# kolorofon.net
KiCad netlist of a schematic drawn in EAGLE
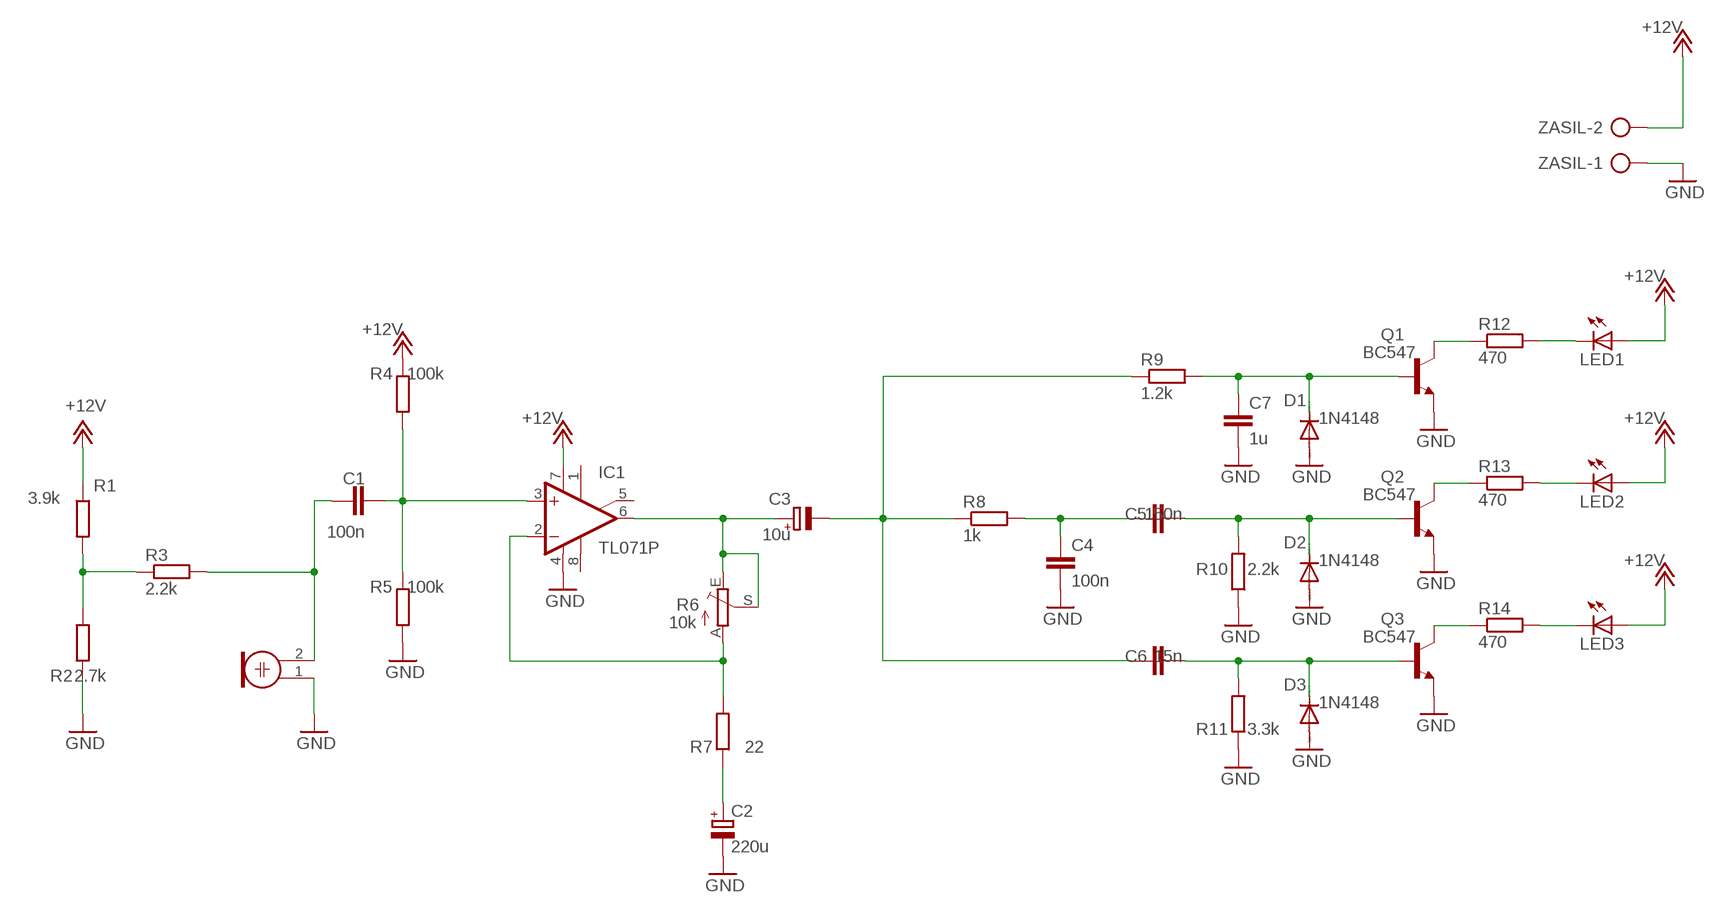
[diagram p0: schematic, sheet 1]

(export (version "E")
  (design (tool "Eeschema 10.0.6"))
  (components
    (comp (ref "C1")
      (value "100n")
      (footprint "eagle-import:C050-025X075")
      (libsource (lib "eagle-import") (part "C-EU050-025X075"))
    )
    (comp (ref "C2")
      (value "220u")
      (footprint "eagle-import:E2,5-6E")
      (libsource (lib "eagle-import") (part "resistor_CPOL-EUE2,5-6E"))
    )
    (comp (ref "C3")
      (value "10u")
      (footprint "eagle-import:E2-5")
      (libsource (lib "eagle-import") (part "CPOL-EUE2-5"))
    )
    (comp (ref "C4")
      (value "100n")
      (footprint "eagle-import:C050-025X075")
      (libsource (lib "eagle-import") (part "C-EU050-025X075"))
    )
    (comp (ref "C5")
      (value "150n")
      (footprint "eagle-import:C050-025X075")
      (libsource (lib "eagle-import") (part "C-EU050-025X075"))
    )
    (comp (ref "C6")
      (value "15n")
      (footprint "eagle-import:C050-025X075")
      (libsource (lib "eagle-import") (part "C-EU050-025X075"))
    )
    (comp (ref "C7")
      (value "1u")
      (footprint "eagle-import:C050-045X075")
      (libsource (lib "eagle-import") (part "C-EU050-045X075"))
    )
    (comp (ref "D1")
      (value "1N4148")
      (footprint "eagle-import:DO35-7")
      (libsource (lib "eagle-import") (part "1N4148DO35-7"))
    )
    (comp (ref "D2")
      (value "1N4148")
      (footprint "eagle-import:DO35-7")
      (libsource (lib "eagle-import") (part "1N4148DO35-7"))
    )
    (comp (ref "D3")
      (value "1N4148")
      (footprint "eagle-import:DO35-7")
      (libsource (lib "eagle-import") (part "1N4148DO35-7"))
    )
    (comp (ref "IC1")
      (value "TL071P")
      (footprint "eagle-import:DIL08")
      (libsource (lib "eagle-import") (part "TL071P"))
    )
    (comp (ref "LED1")
      (value "LED5MM")
      (footprint "eagle-import:LED5MM")
      (libsource (lib "eagle-import") (part "LED5MM"))
    )
    (comp (ref "LED2")
      (value "LED5MM")
      (footprint "eagle-import:LED5MM")
      (libsource (lib "eagle-import") (part "LED5MM"))
    )
    (comp (ref "LED3")
      (value "LED5MM")
      (footprint "eagle-import:LED5MM")
      (libsource (lib "eagle-import") (part "LED5MM"))
    )
    (comp (ref "M1")
      (value "WM.64PN")
      (footprint "eagle-import:WM-64PN")
      (libsource (lib "eagle-import") (part "ELECTRET_MICROPHON-WM.64PN"))
    )
    (comp (ref "Q1")
      (value "BC547")
      (footprint "eagle-import:TO92")
      (libsource (lib "eagle-import") (part "BC547"))
    )
    (comp (ref "Q2")
      (value "BC547")
      (footprint "eagle-import:TO92")
      (libsource (lib "eagle-import") (part "BC547"))
    )
    (comp (ref "Q3")
      (value "BC547")
      (footprint "eagle-import:TO92")
      (libsource (lib "eagle-import") (part "BC547"))
    )
    (comp (ref "R1")
      (value "3.9k")
      (footprint "eagle-import:0204_7")
      (libsource (lib "eagle-import") (part "R-EU_0204/7"))
    )
    (comp (ref "R2")
      (value "2.7k")
      (footprint "eagle-import:0204_7")
      (libsource (lib "eagle-import") (part "R-EU_0204/7"))
    )
    (comp (ref "R3")
      (value "2.2k")
      (footprint "eagle-import:0204_7")
      (libsource (lib "eagle-import") (part "R-EU_0204/7"))
    )
    (comp (ref "R4")
      (value "100k")
      (footprint "eagle-import:0204_7")
      (libsource (lib "eagle-import") (part "R-EU_0204/7"))
    )
    (comp (ref "R5")
      (value "100k")
      (footprint "eagle-import:0204_7")
      (libsource (lib "eagle-import") (part "R-EU_0204/7"))
    )
    (comp (ref "R6")
      (value "10k")
      (footprint "eagle-import:S64Y")
      (libsource (lib "eagle-import") (part "TRIM_EU-S64Y"))
    )
    (comp (ref "R7")
      (value "22")
      (footprint "eagle-import:0204_7")
      (libsource (lib "eagle-import") (part "R-EU_0204/7"))
    )
    (comp (ref "R8")
      (value "1k")
      (footprint "eagle-import:0204_7")
      (libsource (lib "eagle-import") (part "R-EU_0204/7"))
    )
    (comp (ref "R9")
      (value "1.2k")
      (footprint "eagle-import:0204_7")
      (libsource (lib "eagle-import") (part "R-EU_0204/7"))
    )
    (comp (ref "R10")
      (value "2.2k")
      (footprint "eagle-import:0204_7")
      (libsource (lib "eagle-import") (part "R-EU_0204/7"))
    )
    (comp (ref "R11")
      (value "3.3k")
      (footprint "eagle-import:0204_7")
      (libsource (lib "eagle-import") (part "R-EU_0204/7"))
    )
    (comp (ref "R12")
      (value "470")
      (footprint "eagle-import:0204_7")
      (libsource (lib "eagle-import") (part "R-EU_0204/7"))
    )
    (comp (ref "R13")
      (value "470")
      (footprint "eagle-import:0204_7")
      (libsource (lib "eagle-import") (part "R-EU_0204/7"))
    )
    (comp (ref "R14")
      (value "470")
      (footprint "eagle-import:0204_7")
      (libsource (lib "eagle-import") (part "R-EU_0204/7"))
    )
    (comp (ref "ZASIL")
      (value "AK300/2")
      (footprint "eagle-import:AK300_2")
      (libsource (lib "eagle-import") (part "AK300/2"))
    )
  )
  (nets
    (net (code "1") (name "+12V") (class "Default")
      (node (ref "IC1") (pin "7") (pinfunction "V+_7") (pintype "power_in"))
      (node (ref "LED1") (pin "A") (pinfunction "A_A") (pintype "passive"))
      (node (ref "LED2") (pin "A") (pinfunction "A_A") (pintype "passive"))
      (node (ref "LED3") (pin "A") (pinfunction "A_A") (pintype "passive"))
      (node (ref "R1") (pin "1") (pinfunction "1_1") (pintype "passive"))
      (node (ref "R4") (pin "2") (pinfunction "2_2") (pintype "passive"))
      (node (ref "ZASIL") (pin "2") (pinfunction "KL_2") (pintype "passive"))
    )
    (net (code "2") (name "GND") (class "Default")
      (node (ref "C2") (pin "-") (pinfunction "-_-") (pintype "passive"))
      (node (ref "C4") (pin "2") (pinfunction "2_2") (pintype "passive"))
      (node (ref "C7") (pin "2") (pinfunction "2_2") (pintype "passive"))
      (node (ref "D1") (pin "A") (pinfunction "A_A") (pintype "passive"))
      (node (ref "D2") (pin "A") (pinfunction "A_A") (pintype "passive"))
      (node (ref "D3") (pin "A") (pinfunction "A_A") (pintype "passive"))
      (node (ref "IC1") (pin "4") (pinfunction "V-_4") (pintype "power_in"))
      (node (ref "M1") (pin "1") (pinfunction "1_1") (pintype "passive"))
      (node (ref "Q1") (pin "1") (pinfunction "E_1") (pintype "passive"))
      (node (ref "Q2") (pin "1") (pinfunction "E_1") (pintype "passive"))
      (node (ref "Q3") (pin "1") (pinfunction "E_1") (pintype "passive"))
      (node (ref "R10") (pin "1") (pinfunction "1_1") (pintype "passive"))
      (node (ref "R11") (pin "1") (pinfunction "1_1") (pintype "passive"))
      (node (ref "R2") (pin "1") (pinfunction "1_1") (pintype "passive"))
      (node (ref "R5") (pin "1") (pinfunction "1_1") (pintype "passive"))
      (node (ref "ZASIL") (pin "1") (pinfunction "KL_1") (pintype "passive"))
    )
    (net (code "3") (name "Net-(C1-Pad1)") (class "Default")
      (node (ref "C1") (pin "1") (pinfunction "1_1") (pintype "passive"))
      (node (ref "M1") (pin "2") (pinfunction "2_2") (pintype "passive"))
      (node (ref "R3") (pin "2") (pinfunction "2_2") (pintype "passive"))
    )
    (net (code "4") (name "Net-(C2-Pad+)") (class "Default")
      (node (ref "C2") (pin "+") (pinfunction "+_+") (pintype "passive"))
      (node (ref "R7") (pin "1") (pinfunction "1_1") (pintype "passive"))
    )
    (net (code "5") (name "Net-(C3-Pad-)") (class "Default")
      (node (ref "C3") (pin "-") (pinfunction "-_-") (pintype "passive"))
      (node (ref "C6") (pin "1") (pinfunction "1_1") (pintype "passive"))
      (node (ref "R8") (pin "1") (pinfunction "1_1") (pintype "passive"))
      (node (ref "R9") (pin "1") (pinfunction "1_1") (pintype "passive"))
    )
    (net (code "6") (name "Net-(C4-Pad1)") (class "Default")
      (node (ref "C4") (pin "1") (pinfunction "1_1") (pintype "passive"))
      (node (ref "C5") (pin "1") (pinfunction "1_1") (pintype "passive"))
      (node (ref "R8") (pin "2") (pinfunction "2_2") (pintype "passive"))
    )
    (net (code "7") (name "Net-(IC1-+IN)") (class "Default")
      (node (ref "C1") (pin "2") (pinfunction "2_2") (pintype "passive"))
      (node (ref "IC1") (pin "3") (pinfunction "+IN_3") (pintype "input"))
      (node (ref "R4") (pin "1") (pinfunction "1_1") (pintype "passive"))
      (node (ref "R5") (pin "2") (pinfunction "2_2") (pintype "passive"))
    )
    (net (code "8") (name "Net-(IC1--IN)") (class "Default")
      (node (ref "IC1") (pin "2") (pinfunction "-IN_2") (pintype "input"))
      (node (ref "R6") (pin "A") (pinfunction "A_A") (pintype "passive"))
      (node (ref "R7") (pin "2") (pinfunction "2_2") (pintype "passive"))
    )
    (net (code "9") (name "Net-(IC1-OUT)") (class "Default")
      (node (ref "C3") (pin "+") (pinfunction "+_+") (pintype "passive"))
      (node (ref "IC1") (pin "6") (pinfunction "OUT_6") (pintype "output"))
      (node (ref "R6") (pin "E") (pinfunction "E_E") (pintype "passive"))
      (node (ref "R6") (pin "S") (pinfunction "S_S") (pintype "passive"))
    )
    (net (code "10") (name "Net-(LED1-C)") (class "Default")
      (node (ref "LED1") (pin "K") (pinfunction "C_K") (pintype "passive"))
      (node (ref "R12") (pin "2") (pinfunction "2_2") (pintype "passive"))
    )
    (net (code "11") (name "Net-(LED2-C)") (class "Default")
      (node (ref "LED2") (pin "K") (pinfunction "C_K") (pintype "passive"))
      (node (ref "R13") (pin "2") (pinfunction "2_2") (pintype "passive"))
    )
    (net (code "12") (name "Net-(LED3-C)") (class "Default")
      (node (ref "LED3") (pin "K") (pinfunction "C_K") (pintype "passive"))
      (node (ref "R14") (pin "2") (pinfunction "2_2") (pintype "passive"))
    )
    (net (code "13") (name "Net-(Q1-B)") (class "Default")
      (node (ref "C7") (pin "1") (pinfunction "1_1") (pintype "passive"))
      (node (ref "D1") (pin "C") (pinfunction "C_C") (pintype "passive"))
      (node (ref "Q1") (pin "2") (pinfunction "B_2") (pintype "passive"))
      (node (ref "R9") (pin "2") (pinfunction "2_2") (pintype "passive"))
    )
    (net (code "14") (name "Net-(Q1-C)") (class "Default")
      (node (ref "Q1") (pin "3") (pinfunction "C_3") (pintype "passive"))
      (node (ref "R12") (pin "1") (pinfunction "1_1") (pintype "passive"))
    )
    (net (code "15") (name "Net-(Q2-B)") (class "Default")
      (node (ref "C5") (pin "2") (pinfunction "2_2") (pintype "passive"))
      (node (ref "D2") (pin "C") (pinfunction "C_C") (pintype "passive"))
      (node (ref "Q2") (pin "2") (pinfunction "B_2") (pintype "passive"))
      (node (ref "R10") (pin "2") (pinfunction "2_2") (pintype "passive"))
    )
    (net (code "16") (name "Net-(Q2-C)") (class "Default")
      (node (ref "Q2") (pin "3") (pinfunction "C_3") (pintype "passive"))
      (node (ref "R13") (pin "1") (pinfunction "1_1") (pintype "passive"))
    )
    (net (code "17") (name "Net-(Q3-B)") (class "Default")
      (node (ref "C6") (pin "2") (pinfunction "2_2") (pintype "passive"))
      (node (ref "D3") (pin "C") (pinfunction "C_C") (pintype "passive"))
      (node (ref "Q3") (pin "2") (pinfunction "B_2") (pintype "passive"))
      (node (ref "R11") (pin "2") (pinfunction "2_2") (pintype "passive"))
    )
    (net (code "18") (name "Net-(Q3-C)") (class "Default")
      (node (ref "Q3") (pin "3") (pinfunction "C_3") (pintype "passive"))
      (node (ref "R14") (pin "1") (pinfunction "1_1") (pintype "passive"))
    )
    (net (code "19") (name "Net-(R1-Pad2)") (class "Default")
      (node (ref "R1") (pin "2") (pinfunction "2_2") (pintype "passive"))
      (node (ref "R2") (pin "2") (pinfunction "2_2") (pintype "passive"))
      (node (ref "R3") (pin "1") (pinfunction "1_1") (pintype "passive"))
    )
    (net (code "20") (name "unconnected-(IC1-ON1-Pad1)") (class "Default")
      (node (ref "IC1") (pin "1") (pinfunction "ON1_1") (pintype "passive"))
    )
    (net (code "21") (name "unconnected-(IC1-ON2-Pad5)") (class "Default")
      (node (ref "IC1") (pin "5") (pinfunction "ON2_5") (pintype "passive"))
    )
    (net (code "22") (name "unconnected-(IC1-OPT-Pad8)") (class "Default")
      (node (ref "IC1") (pin "8") (pinfunction "OPT_8") (pintype "passive"))
    )
  )
)
